# SEC_POWER.net
KiCad netlist of a schematic drawn in Altium Designer
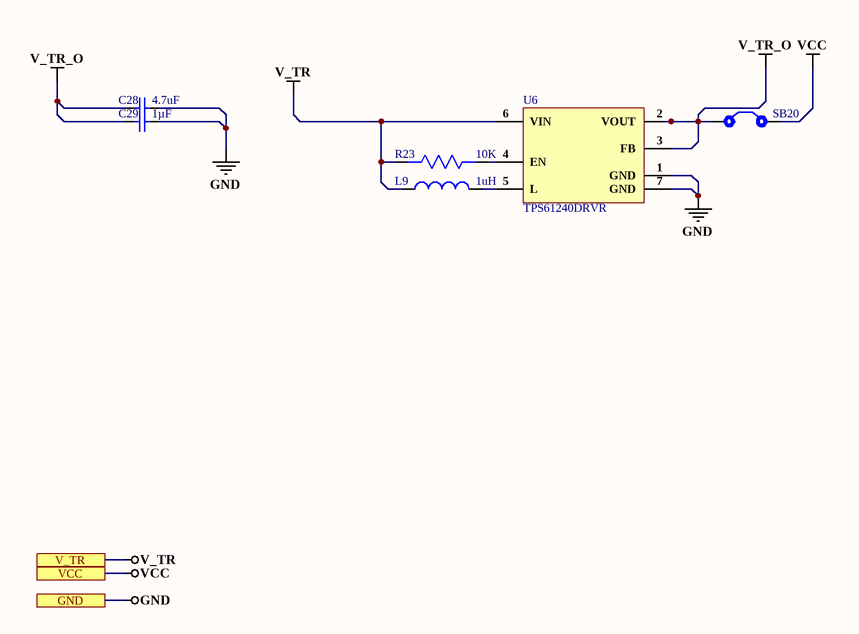
[diagram p0: SEC_POWER.SchDoc]

(export (version "E")
  (design (tool "Eeschema 10.0.6"))
  (components
    (comp (ref "C28")
      (value "4.7uF")
      (footprint "Cap0402")
      (description "CAP CER 4.7UF 6.3V X5R 0402")
      (fields
        (field (name "MANUFACTURER") "Yageo")
        (field (name "MANUFACTURER PART NUMBER") "CC0402MRX5R5BB475")
      )
      (libsource (lib "TT_IntLib") (part "CC0402MRX5R5BB475"))
    )
    (comp (ref "C29")
      (value "1µF")
      (footprint "Cap0402")
      (description "CAP CER 1UF 25V X5R 0402")
      (fields
        (field (name "MANUFACTURER") "Murata")
        (field (name "MANUFACTURER PART NUMBER") "GRM155R61E105KA12D")
      )
      (libsource (lib "TT_IntLib") (part "GRM155R61E105KA12D"))
    )
    (comp (ref "L9")
      (value "1uH")
      (footprint "IND 0603")
      (description "1uH ±20% 1A 180mΩ 0603 Inductors")
      (fields (field (name "MANUFACTURER") "microgate") (field (name "TOLERANCE") "±20%"))
      (libsource (lib "TT_IntLib") (part "MGFL1608F1R0MT-LF"))
    )
    (comp (ref "R23")
      (value "10K")
      (footprint "Res-0201")
      (description "RES SMD 10K OHM 1% 1/20W 0201")
      (fields
        (field (name "MANUFACTURER") "Yageo")
        (field (name "MANUFACTURER PART NUMBER") "RC0201FR-0710KL")
      )
      (libsource (lib "TT_IntLib") (part "RC0201FR-0710KL"))
    )
    (comp (ref "SB20")
      (value "Solder Bridge")
      (footprint "Solder Bridge")
      (description "Solder Bridge ON")
      (libsource (lib "TT_IntLib") (part "Solder Bridge"))
    )
    (comp (ref "U6")
      (value "TPS61240DRVR")
      (footprint "TPS61240DRVR")
      (description "IC REG BOOST SYNC 5V 0.45A 6SON")
      (fields (field (name "MANUFACTURER") "Texas Instruments"))
      (libsource (lib "TT_IntLib") (part "TPS61240DRVR"))
    )
  )
  (nets
    (net (code "1") (name "GND") (class "Default")
      (node (ref "C28") (pin "1") (pintype "passive"))
      (node (ref "C29") (pin "1") (pintype "passive"))
      (node (ref "U6") (pin "1") (pinfunction "GND_1") (pintype "passive"))
      (node (ref "U6") (pin "7") (pinfunction "GND_7") (pintype "passive"))
    )
    (net (code "2") (name "Net-(U6-EN)") (class "Default")
      (node (ref "R23") (pin "1") (pintype "passive"))
      (node (ref "U6") (pin "4") (pinfunction "EN_4") (pintype "passive"))
    )
    (net (code "3") (name "Net-(U6-L)") (class "Default")
      (node (ref "L9") (pin "2") (pinfunction "2_2") (pintype "passive"))
      (node (ref "U6") (pin "5") (pinfunction "L_5") (pintype "passive"))
    )
    (net (code "4") (name "VCC") (class "Default")
      (node (ref "SB20") (pin "2") (pinfunction "2_2") (pintype "passive"))
    )
    (net (code "5") (name "V_TR") (class "Default")
      (node (ref "L9") (pin "1") (pinfunction "1_1") (pintype "passive"))
      (node (ref "R23") (pin "2") (pintype "passive"))
      (node (ref "U6") (pin "6") (pinfunction "VIN_6") (pintype "passive"))
    )
    (net (code "6") (name "V_TR_O") (class "Default")
      (node (ref "C28") (pin "2") (pintype "passive"))
      (node (ref "C29") (pin "2") (pintype "passive"))
      (node (ref "SB20") (pin "1") (pinfunction "1_1") (pintype "passive"))
      (node (ref "U6") (pin "2") (pinfunction "VOUT_2") (pintype "passive"))
      (node (ref "U6") (pin "3") (pinfunction "FB_3") (pintype "passive"))
    )
  )
)
